# E801.net
KiCad netlist of a schematic drawn in EAGLE
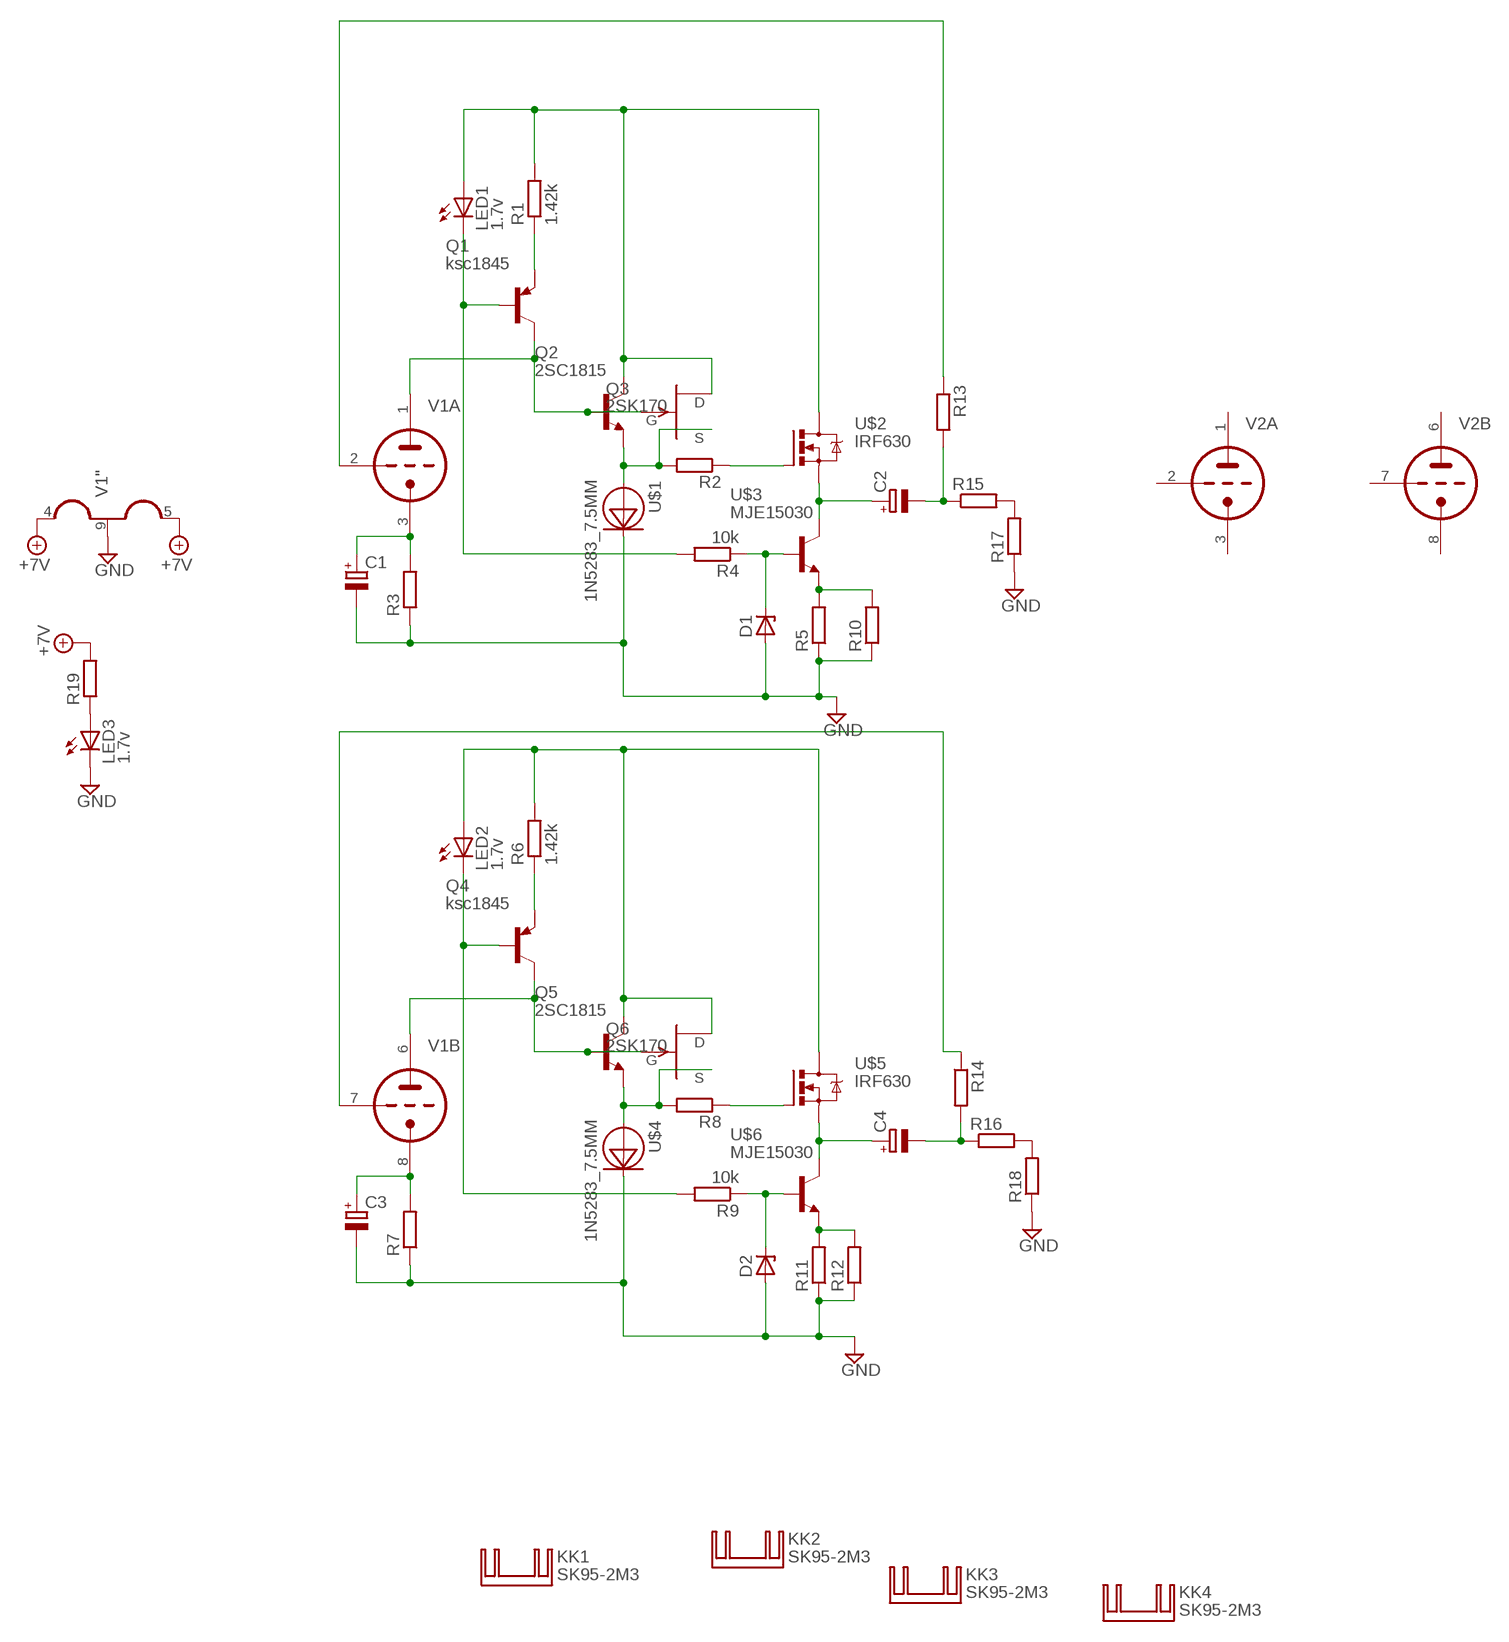
[diagram p0: schematic, sheet 1]

(export (version "E")
  (design (tool "Eeschema 10.0.6"))
  (components
    (comp (ref "C1")
      (value "CPOL-EUE5-10.5")
      (footprint "eagle-import:E5-10,5")
      (libsource (lib "eagle-import") (part "CPOL-EUE5-10.5"))
    )
    (comp (ref "C2")
      (value "CPOL-EUE30-12AXIAL")
      (footprint "eagle-import:E30-12")
      (libsource (lib "eagle-import") (part "CPOL-EUE30-12AXIAL"))
    )
    (comp (ref "C3")
      (value "CPOL-EUE5-10.5")
      (footprint "eagle-import:E5-10,5")
      (libsource (lib "eagle-import") (part "CPOL-EUE5-10.5"))
    )
    (comp (ref "C4")
      (value "CPOL-EUE30-12AXIAL")
      (footprint "eagle-import:E30-12")
      (libsource (lib "eagle-import") (part "CPOL-EUE30-12AXIAL"))
    )
    (comp (ref "D1")
      (value "ZENER-DIODEDO34-7")
      (footprint "eagle-import:DO34Z7")
      (libsource (lib "eagle-import") (part "ZENER-DIODEDO34-7"))
    )
    (comp (ref "D2")
      (value "ZENER-DIODEDO34-7")
      (footprint "eagle-import:DO34Z7")
      (libsource (lib "eagle-import") (part "ZENER-DIODEDO34-7"))
    )
    (comp (ref "KK1")
      (value "SK95-2M3")
      (footprint "eagle-import:SK95-2M3")
      (libsource (lib "eagle-import") (part "SK95-2M3"))
    )
    (comp (ref "KK2")
      (value "SK95-2M3")
      (footprint "eagle-import:SK95-2M3")
      (libsource (lib "eagle-import") (part "SK95-2M3"))
    )
    (comp (ref "KK3")
      (value "SK95-2M3")
      (footprint "eagle-import:SK95-2M3")
      (libsource (lib "eagle-import") (part "SK95-2M3"))
    )
    (comp (ref "KK4")
      (value "SK95-2M3")
      (footprint "eagle-import:SK95-2M3")
      (libsource (lib "eagle-import") (part "SK95-2M3"))
    )
    (comp (ref "LED1")
      (value "1.7v")
      (footprint "eagle-import:LED5MM")
      (libsource (lib "eagle-import") (part "LED5MM"))
    )
    (comp (ref "LED2")
      (value "1.7v")
      (footprint "eagle-import:LED5MM")
      (libsource (lib "eagle-import") (part "LED5MM"))
    )
    (comp (ref "LED3")
      (value "1.7v")
      (footprint "eagle-import:LED5MM")
      (libsource (lib "eagle-import") (part "LED5MM"))
    )
    (comp (ref "Q1")
      (value "ksc1845")
      (footprint "eagle-import:TO92-BCE")
      (libsource (lib "eagle-import") (part "2SA1015"))
    )
    (comp (ref "Q2")
      (value "2SC1815")
      (footprint "eagle-import:TO92-ECB")
      (libsource (lib "eagle-import") (part "2SC1815"))
    )
    (comp (ref "Q3")
      (value "2SK170")
      (footprint "eagle-import:TO92-")
      (libsource (lib "eagle-import") (part "2SK170"))
    )
    (comp (ref "Q4")
      (value "ksc1845")
      (footprint "eagle-import:TO92-BCE")
      (libsource (lib "eagle-import") (part "2SA1015"))
    )
    (comp (ref "Q5")
      (value "2SC1815")
      (footprint "eagle-import:TO92-ECB")
      (libsource (lib "eagle-import") (part "2SC1815"))
    )
    (comp (ref "Q6")
      (value "2SK170")
      (footprint "eagle-import:TO92-")
      (libsource (lib "eagle-import") (part "2SK170"))
    )
    (comp (ref "R1")
      (value "1.42k")
      (footprint "eagle-import:0207_10")
      (libsource (lib "eagle-import") (part "R-EU_0207/10"))
    )
    (comp (ref "R2")
      (value "R-EU_0207/10")
      (footprint "eagle-import:0207_10")
      (libsource (lib "eagle-import") (part "R-EU_0207/10"))
    )
    (comp (ref "R3")
      (value "R-EU_0207/10")
      (footprint "eagle-import:0207_10")
      (libsource (lib "eagle-import") (part "R-EU_0207/10"))
    )
    (comp (ref "R4")
      (value "10k")
      (footprint "eagle-import:0207_10")
      (libsource (lib "eagle-import") (part "R-EU_0207/10"))
    )
    (comp (ref "R5")
      (value "R-EU_0207/10")
      (footprint "eagle-import:0207_10")
      (libsource (lib "eagle-import") (part "R-EU_0207/10"))
    )
    (comp (ref "R6")
      (value "1.42k")
      (footprint "eagle-import:0207_10")
      (libsource (lib "eagle-import") (part "R-EU_0207/10"))
    )
    (comp (ref "R7")
      (value "R-EU_0207/10")
      (footprint "eagle-import:0207_10")
      (libsource (lib "eagle-import") (part "R-EU_0207/10"))
    )
    (comp (ref "R8")
      (value "R-EU_0207/10")
      (footprint "eagle-import:0207_10")
      (libsource (lib "eagle-import") (part "R-EU_0207/10"))
    )
    (comp (ref "R9")
      (value "10k")
      (footprint "eagle-import:0207_10")
      (libsource (lib "eagle-import") (part "R-EU_0207/10"))
    )
    (comp (ref "R10")
      (value "R-EU_0207/10")
      (footprint "eagle-import:0207_10")
      (libsource (lib "eagle-import") (part "R-EU_0207/10"))
    )
    (comp (ref "R11")
      (value "R-EU_0207/10")
      (footprint "eagle-import:0207_10")
      (libsource (lib "eagle-import") (part "R-EU_0207/10"))
    )
    (comp (ref "R12")
      (value "R-EU_0207/10")
      (footprint "eagle-import:0207_10")
      (libsource (lib "eagle-import") (part "R-EU_0207/10"))
    )
    (comp (ref "R13")
      (value "R-EU_0207/10")
      (footprint "eagle-import:0207_10")
      (libsource (lib "eagle-import") (part "R-EU_0207/10"))
    )
    (comp (ref "R14")
      (value "R-EU_0207/10")
      (footprint "eagle-import:0207_10")
      (libsource (lib "eagle-import") (part "R-EU_0207/10"))
    )
    (comp (ref "R15")
      (value "R-EU_0207/10")
      (footprint "eagle-import:0207_10")
      (libsource (lib "eagle-import") (part "R-EU_0207/10"))
    )
    (comp (ref "R16")
      (value "R-EU_0207/10")
      (footprint "eagle-import:0207_10")
      (libsource (lib "eagle-import") (part "R-EU_0207/10"))
    )
    (comp (ref "R17")
      (value "R-EU_0207/10")
      (footprint "eagle-import:0207_10")
      (libsource (lib "eagle-import") (part "R-EU_0207/10"))
    )
    (comp (ref "R18")
      (value "R-EU_0207/10")
      (footprint "eagle-import:0207_10")
      (libsource (lib "eagle-import") (part "R-EU_0207/10"))
    )
    (comp (ref "R19")
      (value "R-EU_0207/10")
      (footprint "eagle-import:0207_10")
      (libsource (lib "eagle-import") (part "R-EU_0207/10"))
    )
    (comp (ref "U$1")
      (value "1N5283_7.5MM")
      (footprint "eagle-import:DO-35-3")
      (libsource (lib "eagle-import") (part "1N5283_7.5MM"))
    )
    (comp (ref "U$2")
      (value "IRF630")
      (footprint "eagle-import:TO220V")
      (libsource (lib "eagle-import") (part "IRF630"))
    )
    (comp (ref "U$3")
      (value "MJE15030")
      (footprint "eagle-import:TO220KG")
      (libsource (lib "eagle-import") (part "MJE15030"))
    )
    (comp (ref "U$4")
      (value "1N5283_7.5MM")
      (footprint "eagle-import:DO-35-3")
      (libsource (lib "eagle-import") (part "1N5283_7.5MM"))
    )
    (comp (ref "U$5")
      (value "IRF630")
      (footprint "eagle-import:TO220V")
      (libsource (lib "eagle-import") (part "IRF630"))
    )
    (comp (ref "U$6")
      (value "MJE15030")
      (footprint "eagle-import:TO220KG")
      (libsource (lib "eagle-import") (part "MJE15030"))
    )
    (comp (ref "V1")
      (value "12AU7-P")
      (footprint "eagle-import:NOVAL")
      (libsource (lib "eagle-import") (part "12AU7-P"))
    )
    (comp (ref "V2")
      (value "12AU7-P")
      (footprint "eagle-import:NOVAL")
      (libsource (lib "eagle-import") (part "12AU7-P"))
    )
  )
  (nets
    (net (code "1") (name "+7V") (class "Default")
      (node (ref "R19") (pin "2") (pinfunction "2_2") (pintype "passive"))
      (node (ref "V1") (pin "4") (pinfunction "H1_4") (pintype "passive"))
      (node (ref "V1") (pin "5") (pinfunction "H3_5") (pintype "passive"))
    )
    (net (code "2") (name "GND") (class "Default")
      (node (ref "C1") (pin "-") (pinfunction "-_-") (pintype "passive"))
      (node (ref "C3") (pin "-") (pinfunction "-_-") (pintype "passive"))
      (node (ref "D1") (pin "A") (pinfunction "A_A") (pintype "passive"))
      (node (ref "D2") (pin "A") (pinfunction "A_A") (pintype "passive"))
      (node (ref "LED3") (pin "K") (pinfunction "C_K") (pintype "passive"))
      (node (ref "R10") (pin "1") (pinfunction "1_1") (pintype "passive"))
      (node (ref "R11") (pin "1") (pinfunction "1_1") (pintype "passive"))
      (node (ref "R12") (pin "1") (pinfunction "1_1") (pintype "passive"))
      (node (ref "R17") (pin "1") (pinfunction "1_1") (pintype "passive"))
      (node (ref "R18") (pin "1") (pinfunction "1_1") (pintype "passive"))
      (node (ref "R3") (pin "1") (pinfunction "1_1") (pintype "passive"))
      (node (ref "R5") (pin "1") (pinfunction "1_1") (pintype "passive"))
      (node (ref "R7") (pin "1") (pinfunction "1_1") (pintype "passive"))
      (node (ref "U$1") (pin "CATHODE") (pinfunction "CATHODE_CATHODE") (pintype "passive"))
      (node (ref "U$4") (pin "CATHODE") (pinfunction "CATHODE_CATHODE") (pintype "passive"))
      (node (ref "V1") (pin "9") (pinfunction "H2_9") (pintype "passive"))
    )
    (net (code "3") (name "Net-(C2-Pad-)") (class "Default")
      (node (ref "C2") (pin "-") (pinfunction "-_-") (pintype "passive"))
      (node (ref "R13") (pin "2") (pinfunction "2_2") (pintype "passive"))
      (node (ref "R15") (pin "1") (pinfunction "1_1") (pintype "passive"))
    )
    (net (code "4") (name "Net-(C4-Pad-)") (class "Default")
      (node (ref "C4") (pin "-") (pinfunction "-_-") (pintype "passive"))
      (node (ref "R14") (pin "2") (pinfunction "2_2") (pintype "passive"))
      (node (ref "R16") (pin "1") (pinfunction "1_1") (pintype "passive"))
    )
    (net (code "5") (name "Net-(LED1-C)") (class "Default")
      (node (ref "LED1") (pin "K") (pinfunction "C_K") (pintype "passive"))
      (node (ref "Q1") (pin "B") (pinfunction "B_B") (pintype "passive"))
      (node (ref "R4") (pin "2") (pinfunction "2_2") (pintype "passive"))
    )
    (net (code "6") (name "Net-(LED2-C)") (class "Default")
      (node (ref "LED2") (pin "K") (pinfunction "C_K") (pintype "passive"))
      (node (ref "Q4") (pin "B") (pinfunction "B_B") (pintype "passive"))
      (node (ref "R9") (pin "2") (pinfunction "2_2") (pintype "passive"))
    )
    (net (code "7") (name "Net-(LED3-PadA)") (class "Default")
      (node (ref "LED3") (pin "A") (pinfunction "A_A") (pintype "passive"))
      (node (ref "R19") (pin "1") (pinfunction "1_1") (pintype "passive"))
    )
    (net (code "8") (name "Net-(Q1-PadE)") (class "Default")
      (node (ref "Q1") (pin "E") (pinfunction "E_E") (pintype "passive"))
      (node (ref "R1") (pin "1") (pinfunction "1_1") (pintype "passive"))
    )
    (net (code "9") (name "Net-(Q3-D)") (class "Default")
      (node (ref "LED1") (pin "A") (pinfunction "A_A") (pintype "passive"))
      (node (ref "Q2") (pin "C") (pinfunction "C_C") (pintype "passive"))
      (node (ref "Q3") (pin "1") (pinfunction "D_1") (pintype "passive"))
      (node (ref "R1") (pin "2") (pinfunction "2_2") (pintype "passive"))
      (node (ref "U$2") (pin "2") (pinfunction "D_2") (pintype "passive"))
    )
    (net (code "10") (name "Net-(Q3-G)") (class "Default")
      (node (ref "Q1") (pin "C") (pinfunction "C_C") (pintype "passive"))
      (node (ref "Q2") (pin "B") (pinfunction "B_B") (pintype "passive"))
      (node (ref "Q3") (pin "2") (pinfunction "G_2") (pintype "passive"))
      (node (ref "V1") (pin "1") (pinfunction "TA_1") (pintype "passive"))
    )
    (net (code "11") (name "Net-(Q3-S)") (class "Default")
      (node (ref "Q2") (pin "E") (pinfunction "E_E") (pintype "passive"))
      (node (ref "Q3") (pin "3") (pinfunction "S_3") (pintype "passive"))
      (node (ref "R2") (pin "2") (pinfunction "2_2") (pintype "passive"))
      (node (ref "U$1") (pin "ANODE") (pinfunction "ANODE_ANODE") (pintype "passive"))
    )
    (net (code "12") (name "Net-(Q4-PadE)") (class "Default")
      (node (ref "Q4") (pin "E") (pinfunction "E_E") (pintype "passive"))
      (node (ref "R6") (pin "1") (pinfunction "1_1") (pintype "passive"))
    )
    (net (code "13") (name "Net-(Q6-D)") (class "Default")
      (node (ref "LED2") (pin "A") (pinfunction "A_A") (pintype "passive"))
      (node (ref "Q5") (pin "C") (pinfunction "C_C") (pintype "passive"))
      (node (ref "Q6") (pin "1") (pinfunction "D_1") (pintype "passive"))
      (node (ref "R6") (pin "2") (pinfunction "2_2") (pintype "passive"))
      (node (ref "U$5") (pin "2") (pinfunction "D_2") (pintype "passive"))
    )
    (net (code "14") (name "Net-(Q6-G)") (class "Default")
      (node (ref "Q4") (pin "C") (pinfunction "C_C") (pintype "passive"))
      (node (ref "Q5") (pin "B") (pinfunction "B_B") (pintype "passive"))
      (node (ref "Q6") (pin "2") (pinfunction "G_2") (pintype "passive"))
      (node (ref "V1") (pin "6") (pinfunction "TA_6") (pintype "passive"))
    )
    (net (code "15") (name "Net-(Q6-S)") (class "Default")
      (node (ref "Q5") (pin "E") (pinfunction "E_E") (pintype "passive"))
      (node (ref "Q6") (pin "3") (pinfunction "S_3") (pintype "passive"))
      (node (ref "R8") (pin "2") (pinfunction "2_2") (pintype "passive"))
      (node (ref "U$4") (pin "ANODE") (pinfunction "ANODE_ANODE") (pintype "passive"))
    )
    (net (code "16") (name "Net-(R15-Pad2)") (class "Default")
      (node (ref "R15") (pin "2") (pinfunction "2_2") (pintype "passive"))
      (node (ref "R17") (pin "2") (pinfunction "2_2") (pintype "passive"))
    )
    (net (code "17") (name "Net-(R16-Pad2)") (class "Default")
      (node (ref "R16") (pin "2") (pinfunction "2_2") (pintype "passive"))
      (node (ref "R18") (pin "2") (pinfunction "2_2") (pintype "passive"))
    )
    (net (code "18") (name "Net-(U$2-G)") (class "Default")
      (node (ref "R2") (pin "1") (pinfunction "1_1") (pintype "passive"))
      (node (ref "U$2") (pin "1") (pinfunction "G_1") (pintype "passive"))
    )
    (net (code "19") (name "Net-(U$2-S)") (class "Default")
      (node (ref "C2") (pin "+") (pinfunction "+_+") (pintype "passive"))
      (node (ref "U$2") (pin "3") (pinfunction "S_3") (pintype "passive"))
      (node (ref "U$3") (pin "2") (pinfunction "C_2") (pintype "passive"))
    )
    (net (code "20") (name "Net-(U$3-B)") (class "Default")
      (node (ref "D1") (pin "C") (pinfunction "C_C") (pintype "passive"))
      (node (ref "R4") (pin "1") (pinfunction "1_1") (pintype "passive"))
      (node (ref "U$3") (pin "1") (pinfunction "B_1") (pintype "passive"))
    )
    (net (code "21") (name "Net-(U$3-E)") (class "Default")
      (node (ref "R10") (pin "2") (pinfunction "2_2") (pintype "passive"))
      (node (ref "R5") (pin "2") (pinfunction "2_2") (pintype "passive"))
      (node (ref "U$3") (pin "3") (pinfunction "E_3") (pintype "passive"))
    )
    (net (code "22") (name "Net-(U$5-G)") (class "Default")
      (node (ref "R8") (pin "1") (pinfunction "1_1") (pintype "passive"))
      (node (ref "U$5") (pin "1") (pinfunction "G_1") (pintype "passive"))
    )
    (net (code "23") (name "Net-(U$5-S)") (class "Default")
      (node (ref "C4") (pin "+") (pinfunction "+_+") (pintype "passive"))
      (node (ref "U$5") (pin "3") (pinfunction "S_3") (pintype "passive"))
      (node (ref "U$6") (pin "2") (pinfunction "C_2") (pintype "passive"))
    )
    (net (code "24") (name "Net-(U$6-B)") (class "Default")
      (node (ref "D2") (pin "C") (pinfunction "C_C") (pintype "passive"))
      (node (ref "R9") (pin "1") (pinfunction "1_1") (pintype "passive"))
      (node (ref "U$6") (pin "1") (pinfunction "B_1") (pintype "passive"))
    )
    (net (code "25") (name "Net-(U$6-E)") (class "Default")
      (node (ref "R11") (pin "2") (pinfunction "2_2") (pintype "passive"))
      (node (ref "R12") (pin "2") (pinfunction "2_2") (pintype "passive"))
      (node (ref "U$6") (pin "3") (pinfunction "E_3") (pintype "passive"))
    )
    (net (code "26") (name "Net-(V1B-TG)") (class "Default")
      (node (ref "R13") (pin "1") (pinfunction "1_1") (pintype "passive"))
      (node (ref "V1") (pin "2") (pinfunction "TG_2") (pintype "passive"))
    )
    (net (code "27") (name "Net-(V1B-TK)") (class "Default")
      (node (ref "C1") (pin "+") (pinfunction "+_+") (pintype "passive"))
      (node (ref "R3") (pin "2") (pinfunction "2_2") (pintype "passive"))
      (node (ref "V1") (pin "3") (pinfunction "TK_3") (pintype "passive"))
    )
    (net (code "28") (name "Net-(V1C-TG)") (class "Default")
      (node (ref "R14") (pin "1") (pinfunction "1_1") (pintype "passive"))
      (node (ref "V1") (pin "7") (pinfunction "TG_7") (pintype "passive"))
    )
    (net (code "29") (name "Net-(V1C-TK)") (class "Default")
      (node (ref "C3") (pin "+") (pinfunction "+_+") (pintype "passive"))
      (node (ref "R7") (pin "2") (pinfunction "2_2") (pintype "passive"))
      (node (ref "V1") (pin "8") (pinfunction "TK_8") (pintype "passive"))
    )
    (net (code "30") (name "unconnected-(V2B-TA-Pad1)") (class "Default")
      (node (ref "V2") (pin "1") (pinfunction "TA_1") (pintype "passive"))
    )
    (net (code "31") (name "unconnected-(V2B-TG-Pad2)") (class "Default")
      (node (ref "V2") (pin "2") (pinfunction "TG_2") (pintype "passive"))
    )
    (net (code "32") (name "unconnected-(V2B-TK-Pad3)") (class "Default")
      (node (ref "V2") (pin "3") (pinfunction "TK_3") (pintype "passive"))
    )
    (net (code "33") (name "unconnected-(V2C-TA-Pad6)") (class "Default")
      (node (ref "V2") (pin "6") (pinfunction "TA_6") (pintype "passive"))
    )
    (net (code "34") (name "unconnected-(V2C-TG-Pad7)") (class "Default")
      (node (ref "V2") (pin "7") (pinfunction "TG_7") (pintype "passive"))
    )
    (net (code "35") (name "unconnected-(V2C-TK-Pad8)") (class "Default")
      (node (ref "V2") (pin "8") (pinfunction "TK_8") (pintype "passive"))
    )
  )
)
